# DDR3B.net
KiCad netlist of a schematic drawn in Altium Designer
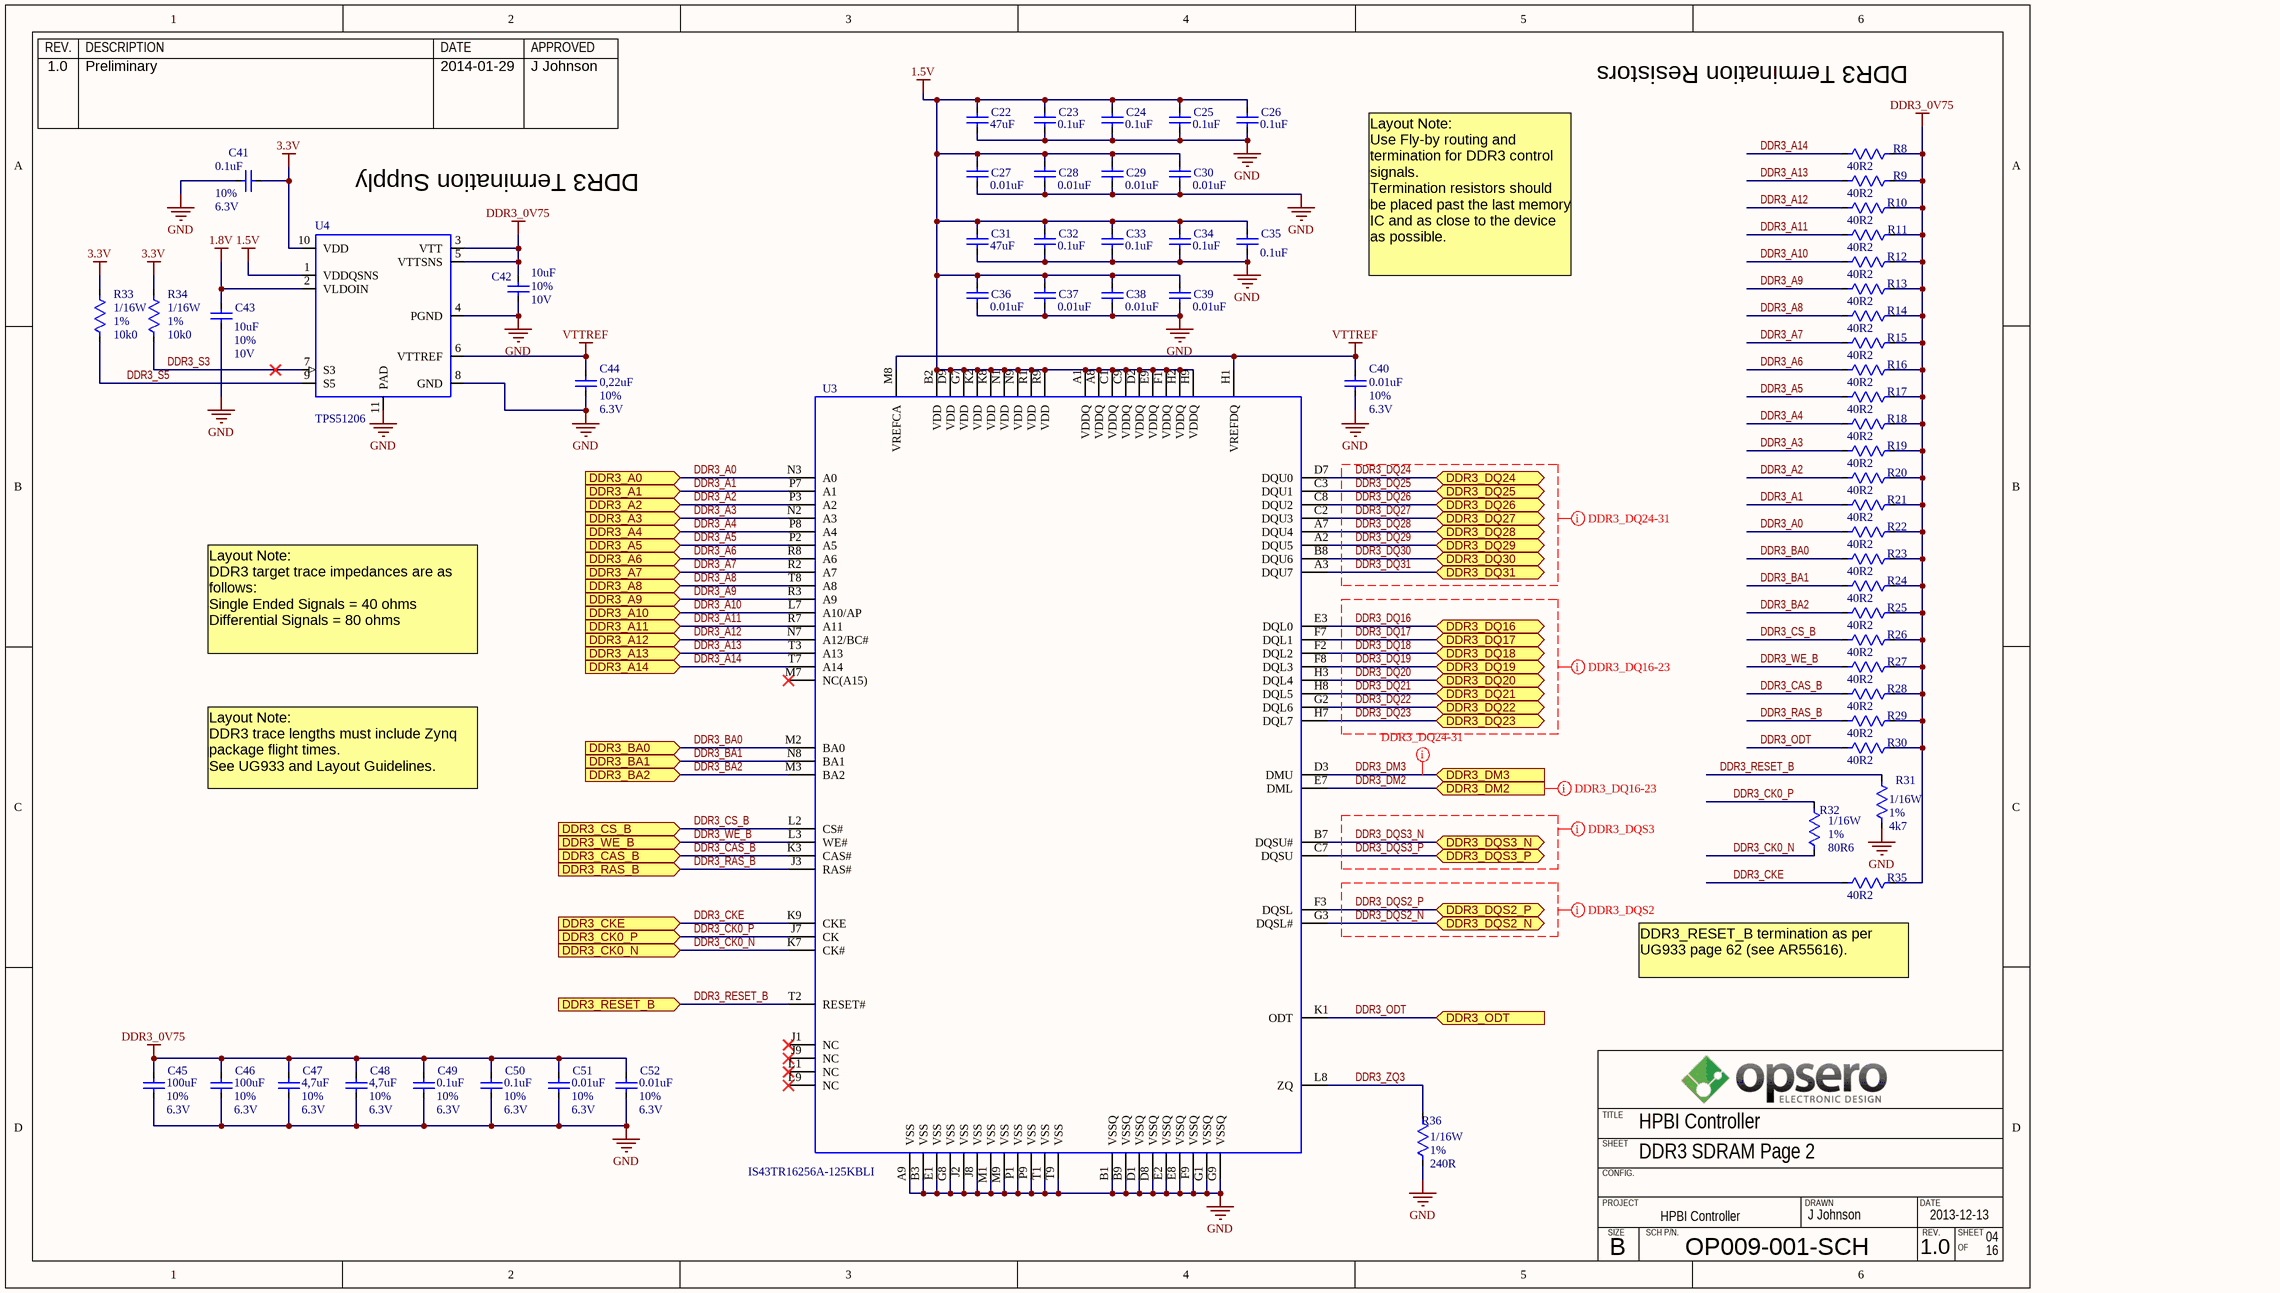
[diagram p0: DDR3B.SchDoc]

(export (version "E")
  (design (tool "Eeschema 10.0.6"))
  (components
    (comp (ref "C22")
      (value "47uF")
      (footprint "CAPC2013X125N")
      (description "Capacitor ceramic, X5R, 47uF, 6.3V, 20%, -55 to +85 C,")
      (fields (field (name "TOLERANCE") "20%") (field (name "VOLTAGE") "6.3V"))
      (libsource (lib "parts") (part "CAPACITOR_NP_TYPE1"))
    )
    (comp (ref "C23")
      (value "0.1uF")
      (footprint "CAPC0603X33N")
      (description "Capacitor ceramic, X5R, 0.1uF, 6.3V, 10%, -55 to +125 C, EIA0201")
      (fields (field (name "TOLERANCE") "10%") (field (name "VOLTAGE") "6.3V"))
      (libsource (lib "parts") (part "CAPACITOR_NP_TYPE1"))
    )
    (comp (ref "C24")
      (value "0.1uF")
      (footprint "CAPC0603X33N")
      (description "Capacitor ceramic, X5R, 0.1uF, 6.3V, 10%, -55 to +125 C, EIA0201")
      (fields (field (name "TOLERANCE") "10%") (field (name "VOLTAGE") "6.3V"))
      (libsource (lib "parts") (part "CAPACITOR_NP_TYPE1"))
    )
    (comp (ref "C25")
      (value "0.1uF")
      (footprint "CAPC0603X33N")
      (description "Capacitor ceramic, X5R, 0.1uF, 6.3V, 10%, -55 to +125 C, EIA0201")
      (fields (field (name "TOLERANCE") "10%") (field (name "VOLTAGE") "6.3V"))
      (libsource (lib "parts") (part "CAPACITOR_NP_TYPE1"))
    )
    (comp (ref "C26")
      (value "0.1uF")
      (footprint "CAPC0603X33N")
      (description "Capacitor ceramic, X5R, 0.1uF, 6.3V, 10%, -55 to +125 C, EIA0201")
      (fields (field (name "TOLERANCE") "10%") (field (name "VOLTAGE") "6.3V"))
      (libsource (lib "parts") (part "CAPACITOR_NP_TYPE1"))
    )
    (comp (ref "C27")
      (value "0.01uF")
      (footprint "CAPC0603X33N")
      (description "Capacitor ceramic, X5R, 0.01uF, 6.3V, 10%, -55 to +125 C, EIA0201")
      (fields (field (name "TOLERANCE") "10%") (field (name "VOLTAGE") "6.3V"))
      (libsource (lib "parts") (part "CAPACITOR_NP_TYPE1"))
    )
    (comp (ref "C28")
      (value "0.01uF")
      (footprint "CAPC0603X33N")
      (description "Capacitor ceramic, X5R, 0.01uF, 6.3V, 10%, -55 to +125 C, EIA0201")
      (fields (field (name "TOLERANCE") "10%") (field (name "VOLTAGE") "6.3V"))
      (libsource (lib "parts") (part "CAPACITOR_NP_TYPE1"))
    )
    (comp (ref "C29")
      (value "0.01uF")
      (footprint "CAPC0603X33N")
      (description "Capacitor ceramic, X5R, 0.01uF, 6.3V, 10%, -55 to +125 C, EIA0201")
      (fields (field (name "TOLERANCE") "10%") (field (name "VOLTAGE") "6.3V"))
      (libsource (lib "parts") (part "CAPACITOR_NP_TYPE1"))
    )
    (comp (ref "C30")
      (value "0.01uF")
      (footprint "CAPC0603X33N")
      (description "Capacitor ceramic, X5R, 0.01uF, 6.3V, 10%, -55 to +125 C, EIA0201")
      (fields (field (name "TOLERANCE") "10%") (field (name "VOLTAGE") "6.3V"))
      (libsource (lib "parts") (part "CAPACITOR_NP_TYPE1"))
    )
    (comp (ref "C31")
      (value "47uF")
      (footprint "CAPC2013X125N")
      (description "Capacitor ceramic, X5R, 47uF, 6.3V, 20%, -55 to +85 C,")
      (fields (field (name "TOLERANCE") "20%") (field (name "VOLTAGE") "6.3V"))
      (libsource (lib "parts") (part "CAPACITOR_NP_TYPE1"))
    )
    (comp (ref "C32")
      (value "0.1uF")
      (footprint "CAPC0603X33N")
      (description "Capacitor ceramic, X5R, 0.1uF, 6.3V, 10%, -55 to +125 C, EIA0201")
      (fields (field (name "TOLERANCE") "10%") (field (name "VOLTAGE") "6.3V"))
      (libsource (lib "parts") (part "CAPACITOR_NP_TYPE1"))
    )
    (comp (ref "C33")
      (value "0.1uF")
      (footprint "CAPC0603X33N")
      (description "Capacitor ceramic, X5R, 0.1uF, 6.3V, 10%, -55 to +125 C, EIA0201")
      (fields (field (name "TOLERANCE") "10%") (field (name "VOLTAGE") "6.3V"))
      (libsource (lib "parts") (part "CAPACITOR_NP_TYPE1"))
    )
    (comp (ref "C34")
      (value "0.1uF")
      (footprint "CAPC0603X33N")
      (description "Capacitor ceramic, X5R, 0.1uF, 6.3V, 10%, -55 to +125 C, EIA0201")
      (fields (field (name "TOLERANCE") "10%") (field (name "VOLTAGE") "6.3V"))
      (libsource (lib "parts") (part "CAPACITOR_NP_TYPE1"))
    )
    (comp (ref "C35")
      (value "0.1uF")
      (footprint "CAPC0603X33N")
      (description "Capacitor ceramic, X5R, 0.1uF, 6.3V, 10%, -55 to +125 C, EIA0201")
      (fields (field (name "TOLERANCE") "10%") (field (name "VOLTAGE") "6.3V"))
      (libsource (lib "parts") (part "CAPACITOR_NP_TYPE1"))
    )
    (comp (ref "C36")
      (value "0.01uF")
      (footprint "CAPC0603X33N")
      (description "Capacitor ceramic, X5R, 0.01uF, 6.3V, 10%, -55 to +125 C, EIA0201")
      (fields (field (name "TOLERANCE") "10%") (field (name "VOLTAGE") "6.3V"))
      (libsource (lib "parts") (part "CAPACITOR_NP_TYPE1"))
    )
    (comp (ref "C37")
      (value "0.01uF")
      (footprint "CAPC0603X33N")
      (description "Capacitor ceramic, X5R, 0.01uF, 6.3V, 10%, -55 to +125 C, EIA0201")
      (fields (field (name "TOLERANCE") "10%") (field (name "VOLTAGE") "6.3V"))
      (libsource (lib "parts") (part "CAPACITOR_NP_TYPE1"))
    )
    (comp (ref "C38")
      (value "0.01uF")
      (footprint "CAPC0603X33N")
      (description "Capacitor ceramic, X5R, 0.01uF, 6.3V, 10%, -55 to +125 C, EIA0201")
      (fields (field (name "TOLERANCE") "10%") (field (name "VOLTAGE") "6.3V"))
      (libsource (lib "parts") (part "CAPACITOR_NP_TYPE1"))
    )
    (comp (ref "C39")
      (value "0.01uF")
      (footprint "CAPC0603X33N")
      (description "Capacitor ceramic, X5R, 0.01uF, 6.3V, 10%, -55 to +125 C, EIA0201")
      (fields (field (name "TOLERANCE") "10%") (field (name "VOLTAGE") "6.3V"))
      (libsource (lib "parts") (part "CAPACITOR_NP_TYPE1"))
    )
    (comp (ref "C40")
      (value "0.01uF")
      (footprint "CAPC0603X33N")
      (description "Capacitor ceramic, X5R, 0.01uF, 6.3V, 10%, -55 to +125 C, EIA0201")
      (fields
        (field (name "TOLERANCE") "10%")
        (field (name "VOLTAGE") "6.3V")
        (field (name "Comment") "CAPACITOR_NP_TYPE1")
      )
      (libsource (lib "parts") (part "CAPACITOR_NP_TYPE1"))
    )
    (comp (ref "C41")
      (value "0.1uF")
      (footprint "CAPC0603X33N")
      (description "Capacitor ceramic, X5R, 0.1uF, 6.3V, 10%, -55 to +125 C, EIA0201")
      (fields
        (field (name "TOLERANCE") "10%")
        (field (name "VOLTAGE") "6.3V")
        (field (name "Comment") "CAPACITOR_NP_TYPE1")
      )
      (libsource (lib "parts") (part "CAPACITOR_NP_TYPE1"))
    )
    (comp (ref "C42")
      (value "10uF")
      (footprint "CAPC1608X38N")
      (description "Capacitor ceramic, X5R, 10uF, 10V, 10%, -55 to +85 C, EIA0603")
      (fields
        (field (name "TOLERANCE") "10%")
        (field (name "VOLTAGE") "10V")
        (field (name "Comment") "CAPACITOR_NP_TYPE1")
      )
      (libsource (lib "parts") (part "CAPACITOR_NP_TYPE1"))
    )
    (comp (ref "C43")
      (value "10uF")
      (footprint "CAPC1608X38N")
      (description "Capacitor ceramic, X5R, 10uF, 10V, 10%, -55 to +85 C, EIA0603")
      (fields
        (field (name "TOLERANCE") "10%")
        (field (name "VOLTAGE") "10V")
        (field (name "Comment") "CAPACITOR_NP_TYPE1")
      )
      (libsource (lib "parts") (part "CAPACITOR_NP_TYPE1"))
    )
    (comp (ref "C44")
      (value "0,22uF")
      (footprint "CAPC1005X55N")
      (description "Capacitor ceramic, X5R, 0.22uF, 6.3V, 10%, -55 to +85 C, EIA0402")
      (fields
        (field (name "TOLERANCE") "10%")
        (field (name "VOLTAGE") "6.3V")
        (field (name "Comment") "CAPACITOR_NP_TYPE1")
      )
      (libsource (lib "parts") (part "CAPACITOR_NP_TYPE1"))
    )
    (comp (ref "C45")
      (value "100uF")
      (footprint "CAPC3225X250N")
      (description "Capacitor ceramic, X5R, 100uF, 6.3V, 10%, -55 to +85 C, EIA1210")
      (fields
        (field (name "TOLERANCE") "10%")
        (field (name "VOLTAGE") "6.3V")
        (field (name "Comment") "CAPACITOR_NP_TYPE1")
      )
      (libsource (lib "parts") (part "CAPACITOR_NP_TYPE1"))
    )
    (comp (ref "C46")
      (value "100uF")
      (footprint "CAPC3225X250N")
      (description "Capacitor ceramic, X5R, 100uF, 6.3V, 10%, -55 to +85 C, EIA1210")
      (fields
        (field (name "TOLERANCE") "10%")
        (field (name "VOLTAGE") "6.3V")
        (field (name "Comment") "CAPACITOR_NP_TYPE1")
      )
      (libsource (lib "parts") (part "CAPACITOR_NP_TYPE1"))
    )
    (comp (ref "C47")
      (value "4,7uF")
      (footprint "CAPC1005X33N")
      (description "Capacitor ceramic, X5R, 4,7uF, 6.3V, 10%, -55 to +85 C, EIA0402")
      (fields
        (field (name "TOLERANCE") "10%")
        (field (name "VOLTAGE") "6.3V")
        (field (name "Comment") "CAPACITOR_NP_TYPE1")
      )
      (libsource (lib "parts") (part "CAPACITOR_NP_TYPE1"))
    )
    (comp (ref "C48")
      (value "4,7uF")
      (footprint "CAPC1005X33N")
      (description "Capacitor ceramic, X5R, 4,7uF, 6.3V, 10%, -55 to +85 C, EIA0402")
      (fields
        (field (name "TOLERANCE") "10%")
        (field (name "VOLTAGE") "6.3V")
        (field (name "Comment") "CAPACITOR_NP_TYPE1")
      )
      (libsource (lib "parts") (part "CAPACITOR_NP_TYPE1"))
    )
    (comp (ref "C49")
      (value "0.1uF")
      (footprint "CAPC0603X33N")
      (description "Capacitor ceramic, X5R, 0.1uF, 6.3V, 10%, -55 to +125 C, EIA0201")
      (fields
        (field (name "TOLERANCE") "10%")
        (field (name "VOLTAGE") "6.3V")
        (field (name "Comment") "CAPACITOR_NP_TYPE1")
      )
      (libsource (lib "parts") (part "CAPACITOR_NP_TYPE1"))
    )
    (comp (ref "C50")
      (value "0.1uF")
      (footprint "CAPC0603X33N")
      (description "Capacitor ceramic, X5R, 0.1uF, 6.3V, 10%, -55 to +125 C, EIA0201")
      (fields
        (field (name "TOLERANCE") "10%")
        (field (name "VOLTAGE") "6.3V")
        (field (name "Comment") "CAPACITOR_NP_TYPE1")
      )
      (libsource (lib "parts") (part "CAPACITOR_NP_TYPE1"))
    )
    (comp (ref "C51")
      (value "0.01uF")
      (footprint "CAPC0603X33N")
      (description "Capacitor ceramic, X5R, 0.01uF, 6.3V, 10%, -55 to +125 C, EIA0201")
      (fields
        (field (name "TOLERANCE") "10%")
        (field (name "VOLTAGE") "6.3V")
        (field (name "Comment") "CAPACITOR_NP_TYPE1")
      )
      (libsource (lib "parts") (part "CAPACITOR_NP_TYPE1"))
    )
    (comp (ref "C52")
      (value "0.01uF")
      (footprint "CAPC0603X33N")
      (description "Capacitor ceramic, X5R, 0.01uF, 6.3V, 10%, -55 to +125 C, EIA0201")
      (fields
        (field (name "TOLERANCE") "10%")
        (field (name "VOLTAGE") "6.3V")
        (field (name "Comment") "CAPACITOR_NP_TYPE1")
      )
      (libsource (lib "parts") (part "CAPACITOR_NP_TYPE1"))
    )
    (comp (ref "R8")
      (value "40R2")
      (footprint "RESC1005X33N")
      (description "Resistor, 40R2, 1/16W, 1%, -50 to +155 C, EIA0402, EIA(M)1005")
      (fields (field (name "VOLTAGE") "50V") (field (name "POWER") "1/16W"))
      (libsource (lib "parts") (part "RESISTOR_TYPE1"))
    )
    (comp (ref "R9")
      (value "40R2")
      (footprint "RESC1005X33N")
      (description "Resistor, 40R2, 1/16W, 1%, -50 to +155 C, EIA0402, EIA(M)1005")
      (fields (field (name "VOLTAGE") "50V") (field (name "POWER") "1/16W"))
      (libsource (lib "parts") (part "RESISTOR_TYPE1"))
    )
    (comp (ref "R10")
      (value "40R2")
      (footprint "RESC1005X33N")
      (description "Resistor, 40R2, 1/16W, 1%, -50 to +155 C, EIA0402, EIA(M)1005")
      (fields (field (name "VOLTAGE") "50V") (field (name "POWER") "1/16W"))
      (libsource (lib "parts") (part "RESISTOR_TYPE1"))
    )
    (comp (ref "R11")
      (value "40R2")
      (footprint "RESC1005X33N")
      (description "Resistor, 40R2, 1/16W, 1%, -50 to +155 C, EIA0402, EIA(M)1005")
      (fields (field (name "VOLTAGE") "50V") (field (name "POWER") "1/16W"))
      (libsource (lib "parts") (part "RESISTOR_TYPE1"))
    )
    (comp (ref "R12")
      (value "40R2")
      (footprint "RESC1005X33N")
      (description "Resistor, 40R2, 1/16W, 1%, -50 to +155 C, EIA0402, EIA(M)1005")
      (fields (field (name "VOLTAGE") "50V") (field (name "POWER") "1/16W"))
      (libsource (lib "parts") (part "RESISTOR_TYPE1"))
    )
    (comp (ref "R13")
      (value "40R2")
      (footprint "RESC1005X33N")
      (description "Resistor, 40R2, 1/16W, 1%, -50 to +155 C, EIA0402, EIA(M)1005")
      (fields (field (name "VOLTAGE") "50V") (field (name "POWER") "1/16W"))
      (libsource (lib "parts") (part "RESISTOR_TYPE1"))
    )
    (comp (ref "R14")
      (value "40R2")
      (footprint "RESC1005X33N")
      (description "Resistor, 40R2, 1/16W, 1%, -50 to +155 C, EIA0402, EIA(M)1005")
      (fields (field (name "VOLTAGE") "50V") (field (name "POWER") "1/16W"))
      (libsource (lib "parts") (part "RESISTOR_TYPE1"))
    )
    (comp (ref "R15")
      (value "40R2")
      (footprint "RESC1005X33N")
      (description "Resistor, 40R2, 1/16W, 1%, -50 to +155 C, EIA0402, EIA(M)1005")
      (fields (field (name "VOLTAGE") "50V") (field (name "POWER") "1/16W"))
      (libsource (lib "parts") (part "RESISTOR_TYPE1"))
    )
    (comp (ref "R16")
      (value "40R2")
      (footprint "RESC1005X33N")
      (description "Resistor, 40R2, 1/16W, 1%, -50 to +155 C, EIA0402, EIA(M)1005")
      (fields (field (name "VOLTAGE") "50V") (field (name "POWER") "1/16W"))
      (libsource (lib "parts") (part "RESISTOR_TYPE1"))
    )
    (comp (ref "R17")
      (value "40R2")
      (footprint "RESC1005X33N")
      (description "Resistor, 40R2, 1/16W, 1%, -50 to +155 C, EIA0402, EIA(M)1005")
      (fields (field (name "VOLTAGE") "50V") (field (name "POWER") "1/16W"))
      (libsource (lib "parts") (part "RESISTOR_TYPE1"))
    )
    (comp (ref "R18")
      (value "40R2")
      (footprint "RESC1005X33N")
      (description "Resistor, 40R2, 1/16W, 1%, -50 to +155 C, EIA0402, EIA(M)1005")
      (fields (field (name "VOLTAGE") "50V") (field (name "POWER") "1/16W"))
      (libsource (lib "parts") (part "RESISTOR_TYPE1"))
    )
    (comp (ref "R19")
      (value "40R2")
      (footprint "RESC1005X33N")
      (description "Resistor, 40R2, 1/16W, 1%, -50 to +155 C, EIA0402, EIA(M)1005")
      (fields (field (name "VOLTAGE") "50V") (field (name "POWER") "1/16W"))
      (libsource (lib "parts") (part "RESISTOR_TYPE1"))
    )
    (comp (ref "R20")
      (value "40R2")
      (footprint "RESC1005X33N")
      (description "Resistor, 40R2, 1/16W, 1%, -50 to +155 C, EIA0402, EIA(M)1005")
      (fields (field (name "VOLTAGE") "50V") (field (name "POWER") "1/16W"))
      (libsource (lib "parts") (part "RESISTOR_TYPE1"))
    )
    (comp (ref "R21")
      (value "40R2")
      (footprint "RESC1005X33N")
      (description "Resistor, 40R2, 1/16W, 1%, -50 to +155 C, EIA0402, EIA(M)1005")
      (fields (field (name "VOLTAGE") "50V") (field (name "POWER") "1/16W"))
      (libsource (lib "parts") (part "RESISTOR_TYPE1"))
    )
    (comp (ref "R22")
      (value "40R2")
      (footprint "RESC1005X33N")
      (description "Resistor, 40R2, 1/16W, 1%, -50 to +155 C, EIA0402, EIA(M)1005")
      (fields (field (name "VOLTAGE") "50V") (field (name "POWER") "1/16W"))
      (libsource (lib "parts") (part "RESISTOR_TYPE1"))
    )
    (comp (ref "R23")
      (value "40R2")
      (footprint "RESC1005X33N")
      (description "Resistor, 40R2, 1/16W, 1%, -50 to +155 C, EIA0402, EIA(M)1005")
      (fields (field (name "VOLTAGE") "50V") (field (name "POWER") "1/16W"))
      (libsource (lib "parts") (part "RESISTOR_TYPE1"))
    )
    (comp (ref "R24")
      (value "40R2")
      (footprint "RESC1005X33N")
      (description "Resistor, 40R2, 1/16W, 1%, -50 to +155 C, EIA0402, EIA(M)1005")
      (fields (field (name "VOLTAGE") "50V") (field (name "POWER") "1/16W"))
      (libsource (lib "parts") (part "RESISTOR_TYPE1"))
    )
    (comp (ref "R25")
      (value "40R2")
      (footprint "RESC1005X33N")
      (description "Resistor, 40R2, 1/16W, 1%, -50 to +155 C, EIA0402, EIA(M)1005")
      (fields (field (name "VOLTAGE") "50V") (field (name "POWER") "1/16W"))
      (libsource (lib "parts") (part "RESISTOR_TYPE1"))
    )
    (comp (ref "R26")
      (value "40R2")
      (footprint "RESC1005X33N")
      (description "Resistor, 40R2, 1/16W, 1%, -50 to +155 C, EIA0402, EIA(M)1005")
      (fields (field (name "VOLTAGE") "50V") (field (name "POWER") "1/16W"))
      (libsource (lib "parts") (part "RESISTOR_TYPE1"))
    )
    (comp (ref "R27")
      (value "40R2")
      (footprint "RESC1005X33N")
      (description "Resistor, 40R2, 1/16W, 1%, -50 to +155 C, EIA0402, EIA(M)1005")
      (fields (field (name "VOLTAGE") "50V") (field (name "POWER") "1/16W"))
      (libsource (lib "parts") (part "RESISTOR_TYPE1"))
    )
    (comp (ref "R28")
      (value "40R2")
      (footprint "RESC1005X33N")
      (description "Resistor, 40R2, 1/16W, 1%, -50 to +155 C, EIA0402, EIA(M)1005")
      (fields (field (name "VOLTAGE") "50V") (field (name "POWER") "1/16W"))
      (libsource (lib "parts") (part "RESISTOR_TYPE1"))
    )
    (comp (ref "R29")
      (value "40R2")
      (footprint "RESC1005X33N")
      (description "Resistor, 40R2, 1/16W, 1%, -50 to +155 C, EIA0402, EIA(M)1005")
      (fields (field (name "VOLTAGE") "50V") (field (name "POWER") "1/16W"))
      (libsource (lib "parts") (part "RESISTOR_TYPE1"))
    )
    (comp (ref "R30")
      (value "40R2")
      (footprint "RESC1005X33N")
      (description "Resistor, 40R2, 1/16W, 1%, -50 to +155 C, EIA0402, EIA(M)1005")
      (fields (field (name "VOLTAGE") "50V") (field (name "POWER") "1/16W"))
      (libsource (lib "parts") (part "RESISTOR_TYPE1"))
    )
    (comp (ref "R31")
      (value "4k7")
      (footprint "RESC1005X33N")
      (description "Resistor, 4k7, 1/16W, 1%, -55 to +155 C, EIA0402")
      (fields (field (name "VOLTAGE") "50V") (field (name "POWER") "1/16W") (field (name "TOLERANCE") "1%"))
      (libsource (lib "parts") (part "RESISTOR_TYPE1"))
    )
    (comp (ref "R32")
      (value "80R6")
      (footprint "RESC1005X33N")
      (description "Resistor, 80R6, 1/16W, 1%, -50 to +155 C, EIA0402, EIA(M)1005")
      (fields (field (name "VOLTAGE") "50V") (field (name "POWER") "1/16W") (field (name "TOLERANCE") "1%"))
      (libsource (lib "parts") (part "RESISTOR_TYPE1"))
    )
    (comp (ref "R33")
      (value "10k0")
      (footprint "RESC1005X33N")
      (description "Resistor, 10k0, 1/16W, 1%, -55 to +155 C, EIA0402")
      (fields (field (name "VOLTAGE") "50V") (field (name "POWER") "1/16W") (field (name "TOLERANCE") "1%"))
      (libsource (lib "parts") (part "RESISTOR_TYPE1"))
    )
    (comp (ref "R34")
      (value "10k0")
      (footprint "RESC1005X33N")
      (description "Resistor, 10k0, 1/16W, 1%, -55 to +155 C, EIA0402")
      (fields (field (name "VOLTAGE") "50V") (field (name "POWER") "1/16W") (field (name "TOLERANCE") "1%"))
      (libsource (lib "parts") (part "RESISTOR_TYPE1"))
    )
    (comp (ref "R35")
      (value "40R2")
      (footprint "RESC1005X33N")
      (description "Resistor, 40R2, 1/16W, 1%, -50 to +155 C, EIA0402, EIA(M)1005")
      (fields (field (name "VOLTAGE") "50V") (field (name "POWER") "1/16W"))
      (libsource (lib "parts") (part "RESISTOR_TYPE1"))
    )
    (comp (ref "R36")
      (value "240R")
      (footprint "RESC1005X33N")
      (description "Resistor, 240R, 1/16W, 1%, -50 to +155 C, EIA0402, EIA(M)1005")
      (fields (field (name "VOLTAGE") "50V") (field (name "POWER") "1/16W") (field (name "TOLERANCE") "1%"))
      (libsource (lib "parts") (part "RESISTOR_TYPE1"))
    )
    (comp (ref "U3")
      (value "IS43TR16256A-125KBLI")
      (footprint "BGA96C80P6X16_900X1300X120")
      (libsource (lib "parts") (part "IS43TR16256A-125KBLI"))
    )
    (comp (ref "U4")
      (value "TPS51206")
      (footprint "DFN40P200X200X75-11N")
      (description "DDR Termination Regulator, -40 to +85 C")
      (fields (field (name "VOLTAGE") "3.3V or 5V"))
      (libsource (lib "parts") (part "TPS51206"))
    )
  )
  (nets
    (net (code "1") (name "/DDR3_A0") (class "Default")
      (node (ref "R22") (pin "2") (pinfunction "2_2") (pintype "passive"))
      (node (ref "U3") (pin "N3") (pinfunction "A0_N3") (pintype "passive"))
    )
    (net (code "2") (name "/DDR3_A1") (class "Default")
      (node (ref "R21") (pin "2") (pinfunction "2_2") (pintype "passive"))
      (node (ref "U3") (pin "P7") (pinfunction "A1_P7") (pintype "passive"))
    )
    (net (code "3") (name "/DDR3_A2") (class "Default")
      (node (ref "R20") (pin "2") (pinfunction "2_2") (pintype "passive"))
      (node (ref "U3") (pin "P3") (pinfunction "A2_P3") (pintype "passive"))
    )
    (net (code "4") (name "/DDR3_A3") (class "Default")
      (node (ref "R19") (pin "2") (pinfunction "2_2") (pintype "passive"))
      (node (ref "U3") (pin "N2") (pinfunction "A3_N2") (pintype "passive"))
    )
    (net (code "5") (name "/DDR3_A4") (class "Default")
      (node (ref "R18") (pin "2") (pinfunction "2_2") (pintype "passive"))
      (node (ref "U3") (pin "P8") (pinfunction "A4_P8") (pintype "passive"))
    )
    (net (code "6") (name "/DDR3_A5") (class "Default")
      (node (ref "R17") (pin "2") (pinfunction "2_2") (pintype "passive"))
      (node (ref "U3") (pin "P2") (pinfunction "A5_P2") (pintype "passive"))
    )
    (net (code "7") (name "/DDR3_A6") (class "Default")
      (node (ref "R16") (pin "2") (pinfunction "2_2") (pintype "passive"))
      (node (ref "U3") (pin "R8") (pinfunction "A6_R8") (pintype "passive"))
    )
    (net (code "8") (name "/DDR3_A7") (class "Default")
      (node (ref "R15") (pin "2") (pinfunction "2_2") (pintype "passive"))
      (node (ref "U3") (pin "R2") (pinfunction "A7_R2") (pintype "passive"))
    )
    (net (code "9") (name "/DDR3_A8") (class "Default")
      (node (ref "R14") (pin "2") (pinfunction "2_2") (pintype "passive"))
      (node (ref "U3") (pin "T8") (pinfunction "A8_T8") (pintype "passive"))
    )
    (net (code "10") (name "/DDR3_A9") (class "Default")
      (node (ref "R13") (pin "2") (pinfunction "2_2") (pintype "passive"))
      (node (ref "U3") (pin "R3") (pinfunction "A9_R3") (pintype "passive"))
    )
    (net (code "11") (name "/DDR3_A10") (class "Default")
      (node (ref "R12") (pin "2") (pinfunction "2_2") (pintype "passive"))
      (node (ref "U3") (pin "L7") (pinfunction "A10/AP_L7") (pintype "passive"))
    )
    (net (code "12") (name "/DDR3_A11") (class "Default")
      (node (ref "R11") (pin "2") (pinfunction "2_2") (pintype "passive"))
      (node (ref "U3") (pin "R7") (pinfunction "A11_R7") (pintype "passive"))
    )
    (net (code "13") (name "/DDR3_A12") (class "Default")
      (node (ref "R10") (pin "2") (pinfunction "2_2") (pintype "passive"))
      (node (ref "U3") (pin "N7") (pinfunction "A12/BC#_N7") (pintype "passive"))
    )
    (net (code "14") (name "/DDR3_A13") (class "Default")
      (node (ref "R9") (pin "2") (pinfunction "2_2") (pintype "passive"))
      (node (ref "U3") (pin "T3") (pinfunction "A13_T3") (pintype "passive"))
    )
    (net (code "15") (name "/DDR3_A14") (class "Default")
      (node (ref "R8") (pin "2") (pinfunction "2_2") (pintype "passive"))
      (node (ref "U3") (pin "T7") (pinfunction "A14_T7") (pintype "passive"))
    )
    (net (code "16") (name "/DDR3_BA0") (class "Default")
      (node (ref "R23") (pin "2") (pinfunction "2_2") (pintype "passive"))
      (node (ref "U3") (pin "M2") (pinfunction "BA0_M2") (pintype "passive"))
    )
    (net (code "17") (name "/DDR3_BA1") (class "Default")
      (node (ref "R24") (pin "2") (pinfunction "2_2") (pintype "passive"))
      (node (ref "U3") (pin "N8") (pinfunction "BA1_N8") (pintype "passive"))
    )
    (net (code "18") (name "/DDR3_BA2") (class "Default")
      (node (ref "R25") (pin "2") (pinfunction "2_2") (pintype "passive"))
      (node (ref "U3") (pin "M3") (pinfunction "BA2_M3") (pintype "passive"))
    )
    (net (code "19") (name "/DDR3_CAS_B") (class "Default")
      (node (ref "R28") (pin "2") (pinfunction "2_2") (pintype "passive"))
      (node (ref "U3") (pin "K3") (pinfunction "CAS#_K3") (pintype "passive"))
    )
    (net (code "20") (name "/DDR3_CK0_N") (class "Default")
      (node (ref "R32") (pin "1") (pinfunction "1_1") (pintype "passive"))
      (node (ref "U3") (pin "K7") (pinfunction "CK#_K7") (pintype "passive"))
    )
    (net (code "21") (name "/DDR3_CK0_P") (class "Default")
      (node (ref "R32") (pin "2") (pinfunction "2_2") (pintype "passive"))
      (node (ref "U3") (pin "J7") (pinfunction "CK_J7") (pintype "passive"))
    )
    (net (code "22") (name "/DDR3_CKE") (class "Default")
      (node (ref "R35") (pin "2") (pinfunction "2_2") (pintype "passive"))
      (node (ref "U3") (pin "K9") (pinfunction "CKE_K9") (pintype "passive"))
    )
    (net (code "23") (name "/DDR3_CS_B") (class "Default")
      (node (ref "R26") (pin "2") (pinfunction "2_2") (pintype "passive"))
      (node (ref "U3") (pin "L2") (pinfunction "CS#_L2") (pintype "passive"))
    )
    (net (code "24") (name "/DDR3_DM2") (class "Default")
      (node (ref "U3") (pin "E7") (pinfunction "DML_E7") (pintype "passive"))
    )
    (net (code "25") (name "/DDR3_DM3") (class "Default")
      (node (ref "U3") (pin "D3") (pinfunction "DMU_D3") (pintype "passive"))
    )
    (net (code "26") (name "/DDR3_DQ16") (class "Default")
      (node (ref "U3") (pin "E3") (pinfunction "DQL0_E3") (pintype "passive"))
    )
    (net (code "27") (name "/DDR3_DQ17") (class "Default")
      (node (ref "U3") (pin "F7") (pinfunction "DQL1_F7") (pintype "passive"))
    )
    (net (code "28") (name "/DDR3_DQ18") (class "Default")
      (node (ref "U3") (pin "F2") (pinfunction "DQL2_F2") (pintype "passive"))
    )
    (net (code "29") (name "/DDR3_DQ19") (class "Default")
      (node (ref "U3") (pin "F8") (pinfunction "DQL3_F8") (pintype "passive"))
    )
    (net (code "30") (name "/DDR3_DQ20") (class "Default")
      (node (ref "U3") (pin "H3") (pinfunction "DQL4_H3") (pintype "passive"))
    )
    (net (code "31") (name "/DDR3_DQ21") (class "Default")
      (node (ref "U3") (pin "H8") (pinfunction "DQL5_H8") (pintype "passive"))
    )
    (net (code "32") (name "/DDR3_DQ22") (class "Default")
      (node (ref "U3") (pin "G2") (pinfunction "DQL6_G2") (pintype "passive"))
    )
    (net (code "33") (name "/DDR3_DQ23") (class "Default")
      (node (ref "U3") (pin "H7") (pinfunction "DQL7_H7") (pintype "passive"))
    )
    (net (code "34") (name "/DDR3_DQ24") (class "Default")
      (node (ref "U3") (pin "D7") (pinfunction "DQU0_D7") (pintype "passive"))
    )
    (net (code "35") (name "/DDR3_DQ25") (class "Default")
      (node (ref "U3") (pin "C3") (pinfunction "DQU1_C3") (pintype "passive"))
    )
    (net (code "36") (name "/DDR3_DQ26") (class "Default")
      (node (ref "U3") (pin "C8") (pinfunction "DQU2_C8") (pintype "passive"))
    )
    (net (code "37") (name "/DDR3_DQ27") (class "Default")
      (node (ref "U3") (pin "C2") (pinfunction "DQU3_C2") (pintype "passive"))
    )
    (net (code "38") (name "/DDR3_DQ28") (class "Default")
      (node (ref "U3") (pin "A7") (pinfunction "DQU4_A7") (pintype "passive"))
    )
    (net (code "39") (name "/DDR3_DQ29") (class "Default")
      (node (ref "U3") (pin "A2") (pinfunction "DQU5_A2") (pintype "passive"))
    )
    (net (code "40") (name "/DDR3_DQ30") (class "Default")
      (node (ref "U3") (pin "B8") (pinfunction "DQU6_B8") (pintype "passive"))
    )
    (net (code "41") (name "/DDR3_DQ31") (class "Default")
      (node (ref "U3") (pin "A3") (pinfunction "DQU7_A3") (pintype "passive"))
    )
    (net (code "42") (name "/DDR3_DQS2_N") (class "Default")
      (node (ref "U3") (pin "G3") (pinfunction "DQSL#_G3") (pintype "passive"))
    )
    (net (code "43") (name "/DDR3_DQS2_P") (class "Default")
      (node (ref "U3") (pin "F3") (pinfunction "DQSL_F3") (pintype "passive"))
    )
    (net (code "44") (name "/DDR3_DQS3_N") (class "Default")
      (node (ref "U3") (pin "B7") (pinfunction "DQSU#_B7") (pintype "passive"))
    )
    (net (code "45") (name "/DDR3_DQS3_P") (class "Default")
      (node (ref "U3") (pin "C7") (pinfunction "DQSU_C7") (pintype "passive"))
    )
    (net (code "46") (name "/DDR3_ODT") (class "Default")
      (node (ref "R30") (pin "2") (pinfunction "2_2") (pintype "passive"))
      (node (ref "U3") (pin "K1") (pinfunction "ODT_K1") (pintype "passive"))
    )
    (net (code "47") (name "/DDR3_RAS_B") (class "Default")
      (node (ref "R29") (pin "2") (pinfunction "2_2") (pintype "passive"))
      (node (ref "U3") (pin "J3") (pinfunction "RAS#_J3") (pintype "passive"))
    )
    (net (code "48") (name "/DDR3_RESET_B") (class "Default")
      (node (ref "R31") (pin "1") (pinfunction "1_1") (pintype "passive"))
      (node (ref "U3") (pin "T2") (pinfunction "RESET#_T2") (pintype "passive"))
    )
    (net (code "49") (name "/DDR3_S3") (class "Default")
      (node (ref "R34") (pin "2") (pinfunction "2_2") (pintype "passive"))
      (node (ref "U4") (pin "7") (pinfunction "S3_7") (pintype "input"))
    )
    (net (code "50") (name "/DDR3_S5") (class "Default")
      (node (ref "R33") (pin "2") (pinfunction "2_2") (pintype "passive"))
      (node (ref "U4") (pin "9") (pinfunction "S5_9") (pintype "passive"))
    )
    (net (code "51") (name "/DDR3_WE_B") (class "Default")
      (node (ref "R27") (pin "2") (pinfunction "2_2") (pintype "passive"))
      (node (ref "U3") (pin "L3") (pinfunction "WE#_L3") (pintype "passive"))
    )
    (net (code "52") (name "/DDR3_ZQ3") (class "Default")
      (node (ref "R36") (pin "2") (pinfunction "2_2") (pintype "passive"))
      (node (ref "U3") (pin "L8") (pinfunction "ZQ_L8") (pintype "passive"))
    )
    (net (code "53") (name "1.5V") (class "Default")
      (node (ref "C22") (pin "1") (pinfunction "1_1") (pintype "passive"))
      (node (ref "C23") (pin "1") (pinfunction "1_1") (pintype "passive"))
      (node (ref "C24") (pin "1") (pinfunction "1_1") (pintype "passive"))
      (node (ref "C25") (pin "1") (pinfunction "1_1") (pintype "passive"))
      (node (ref "C26") (pin "1") (pinfunction "1_1") (pintype "passive"))
      (node (ref "C27") (pin "1") (pinfunction "1_1") (pintype "passive"))
      (node (ref "C28") (pin "1") (pinfunction "1_1") (pintype "passive"))
      (node (ref "C29") (pin "1") (pinfunction "1_1") (pintype "passive"))
      (node (ref "C30") (pin "1") (pinfunction "1_1") (pintype "passive"))
      (node (ref "C31") (pin "1") (pinfunction "1_1") (pintype "passive"))
      (node (ref "C32") (pin "1") (pinfunction "1_1") (pintype "passive"))
      (node (ref "C33") (pin "1") (pinfunction "1_1") (pintype "passive"))
      (node (ref "C34") (pin "1") (pinfunction "1_1") (pintype "passive"))
      (node (ref "C35") (pin "1") (pinfunction "1_1") (pintype "passive"))
      (node (ref "C36") (pin "1") (pinfunction "1_1") (pintype "passive"))
      (node (ref "C37") (pin "1") (pinfunction "1_1") (pintype "passive"))
      (node (ref "C38") (pin "1") (pinfunction "1_1") (pintype "passive"))
      (node (ref "C39") (pin "1") (pinfunction "1_1") (pintype "passive"))
      (node (ref "U3") (pin "A1") (pinfunction "VDDQ_A1") (pintype "passive"))
      (node (ref "U3") (pin "A8") (pinfunction "VDDQ_A8") (pintype "passive"))
      (node (ref "U3") (pin "B2") (pinfunction "VDD_B2") (pintype "passive"))
      (node (ref "U3") (pin "C1") (pinfunction "VDDQ_C1") (pintype "passive"))
      (node (ref "U3") (pin "C9") (pinfunction "VDDQ_C9") (pintype "passive"))
      (node (ref "U3") (pin "D2") (pinfunction "VDDQ_D2") (pintype "passive"))
      (node (ref "U3") (pin "D9") (pinfunction "VDD_D9") (pintype "passive"))
      (node (ref "U3") (pin "E9") (pinfunction "VDDQ_E9") (pintype "passive"))
      (node (ref "U3") (pin "F1") (pinfunction "VDDQ_F1") (pintype "passive"))
      (node (ref "U3") (pin "G7") (pinfunction "VDD_G7") (pintype "passive"))
      (node (ref "U3") (pin "H2") (pinfunction "VDDQ_H2") (pintype "passive"))
      (node (ref "U3") (pin "H9") (pinfunction "VDDQ_H9") (pintype "passive"))
      (node (ref "U3") (pin "K2") (pinfunction "VDD_K2") (pintype "passive"))
      (node (ref "U3") (pin "K8") (pinfunction "VDD_K8") (pintype "passive"))
      (node (ref "U3") (pin "N1") (pinfunction "VDD_N1") (pintype "passive"))
      (node (ref "U3") (pin "N9") (pinfunction "VDD_N9") (pintype "passive"))
      (node (ref "U3") (pin "R1") (pinfunction "VDD_R1") (pintype "passive"))
      (node (ref "U3") (pin "R9") (pinfunction "VDD_R9") (pintype "passive"))
      (node (ref "U4") (pin "1") (pinfunction "VDDQSNS_1") (pintype "power_in"))
    )
    (net (code "54") (name "1.8V") (class "Default")
      (node (ref "C43") (pin "1") (pinfunction "1_1") (pintype "passive"))
      (node (ref "U4") (pin "2") (pinfunction "VLDOIN_2") (pintype "power_in"))
    )
    (net (code "55") (name "3.3V") (class "Default")
      (node (ref "C41") (pin "1") (pinfunction "1_1") (pintype "passive"))
      (node (ref "R33") (pin "1") (pinfunction "1_1") (pintype "passive"))
      (node (ref "R34") (pin "1") (pinfunction "1_1") (pintype "passive"))
      (node (ref "U4") (pin "10") (pinfunction "VDD_10") (pintype "power_in"))
    )
    (net (code "56") (name "DDR3_0V75") (class "Default")
      (node (ref "C42") (pin "1") (pinfunction "1_1") (pintype "passive"))
      (node (ref "C45") (pin "1") (pinfunction "1_1") (pintype "passive"))
      (node (ref "C46") (pin "1") (pinfunction "1_1") (pintype "passive"))
      (node (ref "C47") (pin "1") (pinfunction "1_1") (pintype "passive"))
      (node (ref "C48") (pin "1") (pinfunction "1_1") (pintype "passive"))
      (node (ref "C49") (pin "1") (pinfunction "1_1") (pintype "passive"))
      (node (ref "C50") (pin "1") (pinfunction "1_1") (pintype "passive"))
      (node (ref "C51") (pin "1") (pinfunction "1_1") (pintype "passive"))
      (node (ref "C52") (pin "1") (pinfunction "1_1") (pintype "passive"))
      (node (ref "R10") (pin "1") (pinfunction "1_1") (pintype "passive"))
      (node (ref "R11") (pin "1") (pinfunction "1_1") (pintype "passive"))
      (node (ref "R12") (pin "1") (pinfunction "1_1") (pintype "passive"))
      (node (ref "R13") (pin "1") (pinfunction "1_1") (pintype "passive"))
      (node (ref "R14") (pin "1") (pinfunction "1_1") (pintype "passive"))
      (node (ref "R15") (pin "1") (pinfunction "1_1") (pintype "passive"))
      (node (ref "R16") (pin "1") (pinfunction "1_1") (pintype "passive"))
      (node (ref "R17") (pin "1") (pinfunction "1_1") (pintype "passive"))
      (node (ref "R18") (pin "1") (pinfunction "1_1") (pintype "passive"))
      (node (ref "R19") (pin "1") (pinfunction "1_1") (pintype "passive"))
      (node (ref "R20") (pin "1") (pinfunction "1_1") (pintype "passive"))
      (node (ref "R21") (pin "1") (pinfunction "1_1") (pintype "passive"))
      (node (ref "R22") (pin "1") (pinfunction "1_1") (pintype "passive"))
      (node (ref "R23") (pin "1") (pinfunction "1_1") (pintype "passive"))
      (node (ref "R24") (pin "1") (pinfunction "1_1") (pintype "passive"))
      (node (ref "R25") (pin "1") (pinfunction "1_1") (pintype "passive"))
      (node (ref "R26") (pin "1") (pinfunction "1_1") (pintype "passive"))
      (node (ref "R27") (pin "1") (pinfunction "1_1") (pintype "passive"))
      (node (ref "R28") (pin "1") (pinfunction "1_1") (pintype "passive"))
      (node (ref "R29") (pin "1") (pinfunction "1_1") (pintype "passive"))
      (node (ref "R30") (pin "1") (pinfunction "1_1") (pintype "passive"))
      (node (ref "R35") (pin "1") (pinfunction "1_1") (pintype "passive"))
      (node (ref "R8") (pin "1") (pinfunction "1_1") (pintype "passive"))
      (node (ref "R9") (pin "1") (pinfunction "1_1") (pintype "passive"))
      (node (ref "U4") (pin "3") (pinfunction "VTT_3") (pintype "power_in"))
      (node (ref "U4") (pin "5") (pinfunction "VTTSNS_5") (pintype "power_in"))
    )
    (net (code "57") (name "GND") (class "Default")
      (node (ref "C22") (pin "2") (pinfunction "2_2") (pintype "passive"))
      (node (ref "C23") (pin "2") (pinfunction "2_2") (pintype "passive"))
      (node (ref "C24") (pin "2") (pinfunction "2_2") (pintype "passive"))
      (node (ref "C25") (pin "2") (pinfunction "2_2") (pintype "passive"))
      (node (ref "C26") (pin "2") (pinfunction "2_2") (pintype "passive"))
      (node (ref "C27") (pin "2") (pinfunction "2_2") (pintype "passive"))
      (node (ref "C28") (pin "2") (pinfunction "2_2") (pintype "passive"))
      (node (ref "C29") (pin "2") (pinfunction "2_2") (pintype "passive"))
      (node (ref "C30") (pin "2") (pinfunction "2_2") (pintype "passive"))
      (node (ref "C31") (pin "2") (pinfunction "2_2") (pintype "passive"))
      (node (ref "C32") (pin "2") (pinfunction "2_2") (pintype "passive"))
      (node (ref "C33") (pin "2") (pinfunction "2_2") (pintype "passive"))
      (node (ref "C34") (pin "2") (pinfunction "2_2") (pintype "passive"))
      (node (ref "C35") (pin "2") (pinfunction "2_2") (pintype "passive"))
      (node (ref "C36") (pin "2") (pinfunction "2_2") (pintype "passive"))
      (node (ref "C37") (pin "2") (pinfunction "2_2") (pintype "passive"))
      (node (ref "C38") (pin "2") (pinfunction "2_2") (pintype "passive"))
      (node (ref "C39") (pin "2") (pinfunction "2_2") (pintype "passive"))
      (node (ref "C40") (pin "2") (pinfunction "2_2") (pintype "passive"))
      (node (ref "C41") (pin "2") (pinfunction "2_2") (pintype "passive"))
      (node (ref "C42") (pin "2") (pinfunction "2_2") (pintype "passive"))
      (node (ref "C43") (pin "2") (pinfunction "2_2") (pintype "passive"))
      (node (ref "C44") (pin "2") (pinfunction "2_2") (pintype "passive"))
      (node (ref "C45") (pin "2") (pinfunction "2_2") (pintype "passive"))
      (node (ref "C46") (pin "2") (pinfunction "2_2") (pintype "passive"))
      (node (ref "C47") (pin "2") (pinfunction "2_2") (pintype "passive"))
      (node (ref "C48") (pin "2") (pinfunction "2_2") (pintype "passive"))
      (node (ref "C49") (pin "2") (pinfunction "2_2") (pintype "passive"))
      (node (ref "C50") (pin "2") (pinfunction "2_2") (pintype "passive"))
      (node (ref "C51") (pin "2") (pinfunction "2_2") (pintype "passive"))
      (node (ref "C52") (pin "2") (pinfunction "2_2") (pintype "passive"))
      (node (ref "R31") (pin "2") (pinfunction "2_2") (pintype "passive"))
      (node (ref "R36") (pin "1") (pinfunction "1_1") (pintype "passive"))
      (node (ref "U3") (pin "A9") (pinfunction "VSS_A9") (pintype "passive"))
      (node (ref "U3") (pin "B1") (pinfunction "VSSQ_B1") (pintype "passive"))
      (node (ref "U3") (pin "B3") (pinfunction "VSS_B3") (pintype "passive"))
      (node (ref "U3") (pin "B9") (pinfunction "VSSQ_B9") (pintype "passive"))
      (node (ref "U3") (pin "D1") (pinfunction "VSSQ_D1") (pintype "passive"))
      (node (ref "U3") (pin "D8") (pinfunction "VSSQ_D8") (pintype "passive"))
      (node (ref "U3") (pin "E1") (pinfunction "VSS_E1") (pintype "passive"))
      (node (ref "U3") (pin "E2") (pinfunction "VSSQ_E2") (pintype "passive"))
      (node (ref "U3") (pin "E8") (pinfunction "VSSQ_E8") (pintype "passive"))
      (node (ref "U3") (pin "F9") (pinfunction "VSSQ_F9") (pintype "passive"))
      (node (ref "U3") (pin "G1") (pinfunction "VSSQ_G1") (pintype "passive"))
      (node (ref "U3") (pin "G8") (pinfunction "VSS_G8") (pintype "passive"))
      (node (ref "U3") (pin "G9") (pinfunction "VSSQ_G9") (pintype "passive"))
      (node (ref "U3") (pin "J2") (pinfunction "VSS_J2") (pintype "passive"))
      (node (ref "U3") (pin "J8") (pinfunction "VSS_J8") (pintype "passive"))
      (node (ref "U3") (pin "M1") (pinfunction "VSS_M1") (pintype "passive"))
      (node (ref "U3") (pin "M9") (pinfunction "VSS_M9") (pintype "passive"))
      (node (ref "U3") (pin "P1") (pinfunction "VSS_P1") (pintype "passive"))
      (node (ref "U3") (pin "P9") (pinfunction "VSS_P9") (pintype "passive"))
      (node (ref "U3") (pin "T1") (pinfunction "VSS_T1") (pintype "passive"))
      (node (ref "U3") (pin "T9") (pinfunction "VSS_T9") (pintype "passive"))
      (node (ref "U4") (pin "11") (pinfunction "PAD_11") (pintype "power_in"))
      (node (ref "U4") (pin "4") (pinfunction "PGND_4") (pintype "power_in"))
      (node (ref "U4") (pin "8") (pinfunction "GND_8") (pintype "power_in"))
    )
    (net (code "58") (name "VTTREF") (class "Default")
      (node (ref "C40") (pin "1") (pinfunction "1_1") (pintype "passive"))
      (node (ref "C44") (pin "1") (pinfunction "1_1") (pintype "passive"))
      (node (ref "U3") (pin "H1") (pinfunction "VREFDQ_H1") (pintype "passive"))
      (node (ref "U3") (pin "M8") (pinfunction "VREFCA_M8") (pintype "passive"))
      (node (ref "U4") (pin "6") (pinfunction "VTTREF_6") (pintype "power_in"))
    )
    (net (code "59") (name "unconnected-(U3-NC(A15)-PadM7)") (class "Default")
      (node (ref "U3") (pin "M7") (pinfunction "NC(A15)_M7") (pintype "passive+no_connect"))
    )
    (net (code "60") (name "unconnected-(U3-NC-PadJ1)") (class "Default")
      (node (ref "U3") (pin "J1") (pinfunction "NC_J1") (pintype "passive+no_connect"))
    )
    (net (code "61") (name "unconnected-(U3-NC-PadJ9)") (class "Default")
      (node (ref "U3") (pin "J9") (pinfunction "NC_J9") (pintype "passive+no_connect"))
    )
    (net (code "62") (name "unconnected-(U3-NC-PadL1)") (class "Default")
      (node (ref "U3") (pin "L1") (pinfunction "NC_L1") (pintype "passive+no_connect"))
    )
    (net (code "63") (name "unconnected-(U3-NC-PadL9)") (class "Default")
      (node (ref "U3") (pin "L9") (pinfunction "NC_L9") (pintype "passive+no_connect"))
    )
  )
)
